# Battery_Level_Indicator.net
KiCad netlist of a schematic drawn in Altium Designer
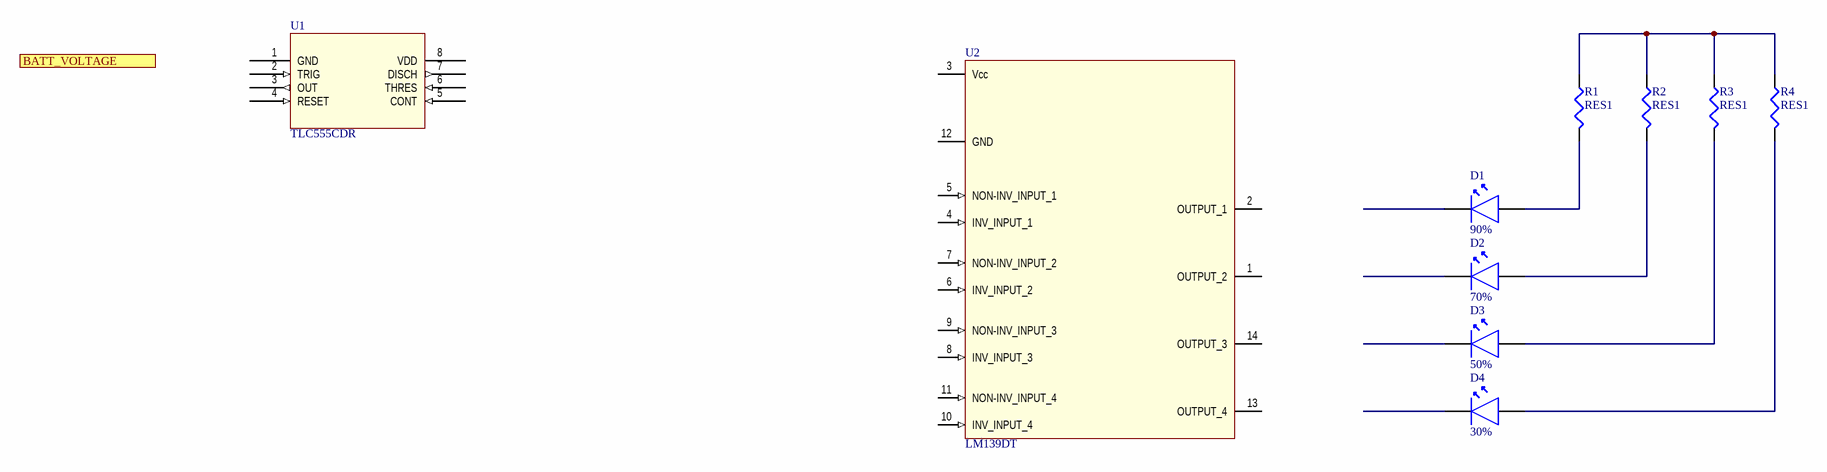
[diagram p0: Battery Level Indicator.SchDoc]

(export (version "E")
  (design (tool "Eeschema 10.0.6"))
  (components
    (comp (ref "D1")
      (value "90%")
      (footprint "WL-SMRW_1205_GRN")
      (libsource (lib "CubeSat-Backplane") (part "LED"))
    )
    (comp (ref "D2")
      (value "70%")
      (footprint "WL-SMRW_1205_GRN")
      (libsource (lib "CubeSat-Backplane") (part "LED"))
    )
    (comp (ref "D3")
      (value "50%")
      (footprint "WL-SMRW_1205_GRN")
      (libsource (lib "CubeSat-Backplane") (part "LED"))
    )
    (comp (ref "D4")
      (value "30%")
      (footprint "WL-SMRW_1205_GRN")
      (libsource (lib "CubeSat-Backplane") (part "LED"))
    )
    (comp (ref "R1")
      (value "RES1")
      (footprint "0603")
      (description "Resistor")
      (libsource (lib "CubeSat-Backplane") (part "RES1"))
    )
    (comp (ref "R2")
      (value "RES1")
      (footprint "0603")
      (description "Resistor")
      (libsource (lib "CubeSat-Backplane") (part "RES1"))
    )
    (comp (ref "R3")
      (value "RES1")
      (footprint "0603")
      (description "Resistor")
      (libsource (lib "CubeSat-Backplane") (part "RES1"))
    )
    (comp (ref "R4")
      (value "RES1")
      (footprint "0603")
      (description "Resistor")
      (libsource (lib "CubeSat-Backplane") (part "RES1"))
    )
    (comp (ref "U1")
      (value "TLC555CD")
      (footprint "D8")
      (description "IC OSC SGL TIMER 2.1MHZ 8-SOIC")
      (fields (field (name "MANUFACTURER PART NUMBER 1") "TLC555CDR"))
      (libsource (lib "CubeSat-Backplane") (part "TLC555CD"))
    )
    (comp (ref "U2")
      (value "LM139DT")
      (footprint "SO-14")
      (description "IC COMP QUAD LOW PWR SO-14")
      (fields (field (name "MANUFACTURER PART NUMBER 1") "LM139DT"))
      (libsource (lib "CubeSat-Backplane") (part "LM139DT"))
    )
  )
  (nets
    (net (code "2") (name "Net-(D1-PadA)") (class "Default")
      (node (ref "D1") (pin "A") (pinfunction "A_A") (pintype "passive"))
      (node (ref "R1") (pin "2") (pinfunction "2_2") (pintype "passive"))
    )
    (net (code "3") (name "Net-(D2-PadA)") (class "Default")
      (node (ref "D2") (pin "A") (pinfunction "A_A") (pintype "passive"))
      (node (ref "R2") (pin "2") (pinfunction "2_2") (pintype "passive"))
    )
    (net (code "4") (name "Net-(D3-PadA)") (class "Default")
      (node (ref "D3") (pin "A") (pinfunction "A_A") (pintype "passive"))
      (node (ref "R3") (pin "2") (pinfunction "2_2") (pintype "passive"))
    )
    (net (code "5") (name "Net-(D4-PadA)") (class "Default")
      (node (ref "D4") (pin "A") (pinfunction "A_A") (pintype "passive"))
      (node (ref "R4") (pin "2") (pinfunction "2_2") (pintype "passive"))
    )
    (net (code "6") (name "Net-(R1-Pad1)") (class "Default")
      (node (ref "R1") (pin "1") (pinfunction "1_1") (pintype "passive"))
      (node (ref "R2") (pin "1") (pinfunction "1_1") (pintype "passive"))
      (node (ref "R3") (pin "1") (pinfunction "1_1") (pintype "passive"))
      (node (ref "R4") (pin "1") (pinfunction "1_1") (pintype "passive"))
    )
    (net (code "7") (name "unconnected-(D1-PadK)") (class "Default")
      (node (ref "D1") (pin "K") (pinfunction "K_K") (pintype "passive"))
    )
    (net (code "8") (name "unconnected-(D2-PadK)") (class "Default")
      (node (ref "D2") (pin "K") (pinfunction "K_K") (pintype "passive"))
    )
    (net (code "9") (name "unconnected-(D3-PadK)") (class "Default")
      (node (ref "D3") (pin "K") (pinfunction "K_K") (pintype "passive"))
    )
    (net (code "10") (name "unconnected-(D4-PadK)") (class "Default")
      (node (ref "D4") (pin "K") (pinfunction "K_K") (pintype "passive"))
    )
    (net (code "11") (name "unconnected-(U1-CONT-Pad5)") (class "Default")
      (node (ref "U1") (pin "5") (pinfunction "CONT_5") (pintype "input"))
    )
    (net (code "12") (name "unconnected-(U1-DISCH-Pad7)") (class "Default")
      (node (ref "U1") (pin "7") (pinfunction "DISCH_7") (pintype "output"))
    )
    (net (code "13") (name "unconnected-(U1-GND-Pad1)") (class "Default")
      (node (ref "U1") (pin "1") (pinfunction "GND_1") (pintype "power_in"))
    )
    (net (code "14") (name "unconnected-(U1-OUT-Pad3)") (class "Default")
      (node (ref "U1") (pin "3") (pinfunction "OUT_3") (pintype "output"))
    )
    (net (code "15") (name "unconnected-(U1-RESET-Pad4)") (class "Default")
      (node (ref "U1") (pin "4") (pinfunction "RESET_4") (pintype "input"))
    )
    (net (code "16") (name "unconnected-(U1-THRES-Pad6)") (class "Default")
      (node (ref "U1") (pin "6") (pinfunction "THRES_6") (pintype "input"))
    )
    (net (code "17") (name "unconnected-(U1-TRIG-Pad2)") (class "Default")
      (node (ref "U1") (pin "2") (pinfunction "TRIG_2") (pintype "input"))
    )
    (net (code "18") (name "unconnected-(U1-VDD-Pad8)") (class "Default")
      (node (ref "U1") (pin "8") (pinfunction "VDD_8") (pintype "power_in"))
    )
    (net (code "19") (name "unconnected-(U2-GND-Pad12)") (class "Default")
      (node (ref "U2") (pin "12") (pinfunction "GND_12") (pintype "power_in"))
    )
    (net (code "20") (name "unconnected-(U2-INV_INPUT_1-Pad4)") (class "Default")
      (node (ref "U2") (pin "4") (pinfunction "INV_INPUT_1_4") (pintype "input"))
    )
    (net (code "21") (name "unconnected-(U2-INV_INPUT_2-Pad6)") (class "Default")
      (node (ref "U2") (pin "6") (pinfunction "INV_INPUT_2_6") (pintype "input"))
    )
    (net (code "22") (name "unconnected-(U2-INV_INPUT_3-Pad8)") (class "Default")
      (node (ref "U2") (pin "8") (pinfunction "INV_INPUT_3_8") (pintype "input"))
    )
    (net (code "23") (name "unconnected-(U2-INV_INPUT_4-Pad10)") (class "Default")
      (node (ref "U2") (pin "10") (pinfunction "INV_INPUT_4_10") (pintype "input"))
    )
    (net (code "24") (name "unconnected-(U2-NON-INV_INPUT_1-Pad5)") (class "Default")
      (node (ref "U2") (pin "5") (pinfunction "NON-INV_INPUT_1_5") (pintype "input"))
    )
    (net (code "25") (name "unconnected-(U2-NON-INV_INPUT_2-Pad7)") (class "Default")
      (node (ref "U2") (pin "7") (pinfunction "NON-INV_INPUT_2_7") (pintype "input"))
    )
    (net (code "26") (name "unconnected-(U2-NON-INV_INPUT_3-Pad9)") (class "Default")
      (node (ref "U2") (pin "9") (pinfunction "NON-INV_INPUT_3_9") (pintype "input"))
    )
    (net (code "27") (name "unconnected-(U2-NON-INV_INPUT_4-Pad11)") (class "Default")
      (node (ref "U2") (pin "11") (pinfunction "NON-INV_INPUT_4_11") (pintype "input"))
    )
    (net (code "28") (name "unconnected-(U2-OUTPUT_1-Pad2)") (class "Default")
      (node (ref "U2") (pin "2") (pinfunction "OUTPUT_1_2") (pintype "open_collector"))
    )
    (net (code "29") (name "unconnected-(U2-OUTPUT_2-Pad1)") (class "Default")
      (node (ref "U2") (pin "1") (pinfunction "OUTPUT_2_1") (pintype "open_collector"))
    )
    (net (code "30") (name "unconnected-(U2-OUTPUT_3-Pad14)") (class "Default")
      (node (ref "U2") (pin "14") (pinfunction "OUTPUT_3_14") (pintype "open_collector"))
    )
    (net (code "31") (name "unconnected-(U2-OUTPUT_4-Pad13)") (class "Default")
      (node (ref "U2") (pin "13") (pinfunction "OUTPUT_4_13") (pintype "open_collector"))
    )
    (net (code "32") (name "unconnected-(U2-Vcc-Pad3)") (class "Default")
      (node (ref "U2") (pin "3") (pinfunction "Vcc_3") (pintype "power_in"))
    )
  )
)
